# smart_bldc_commutator.net
KiCad netlist of a schematic drawn in EAGLE
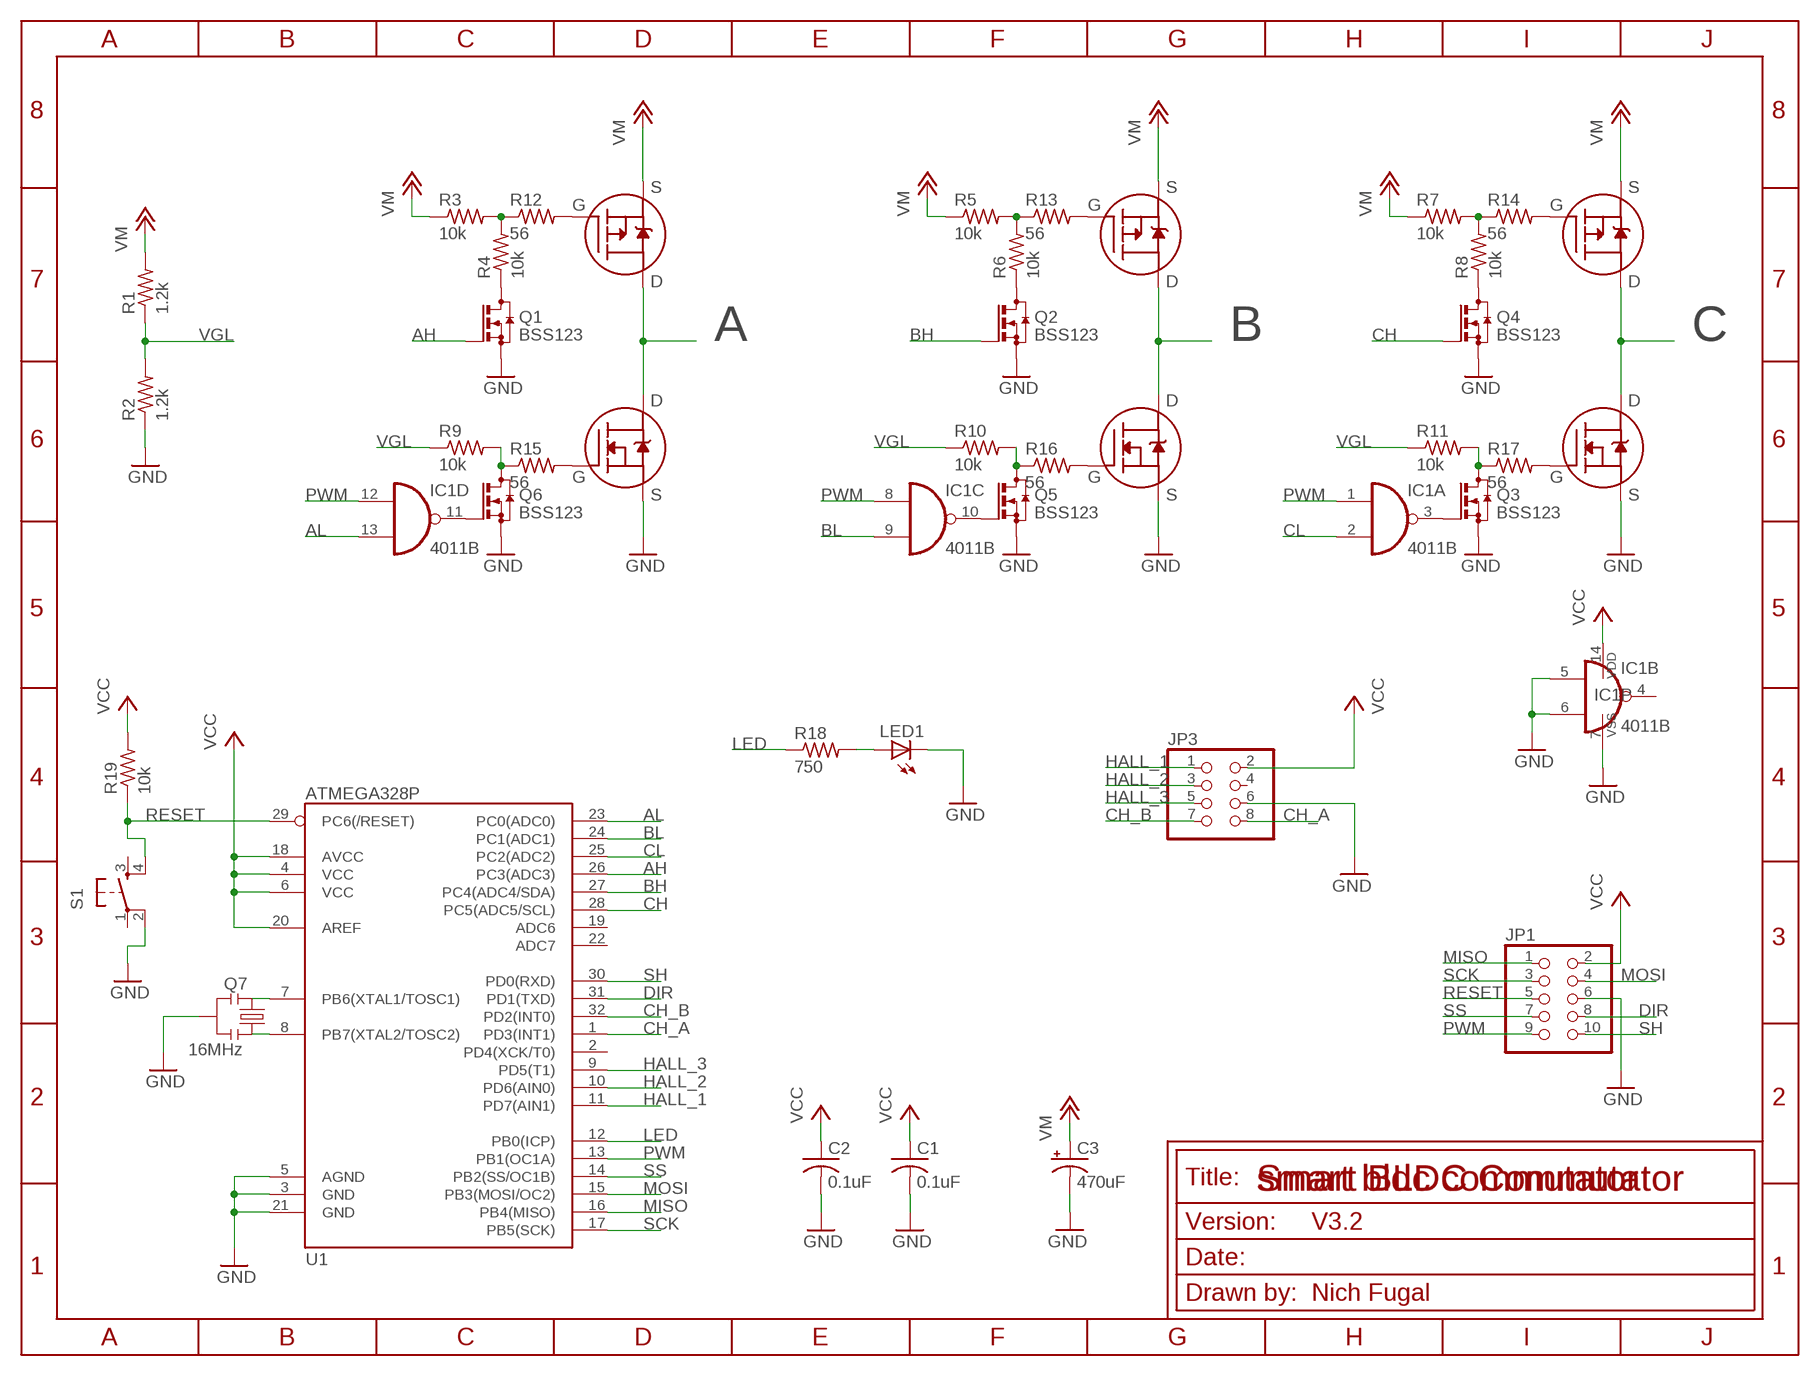
[diagram p0: schematic, sheet 1]

(export (version "E")
  (design (tool "Eeschema 10.0.6"))
  (components
    (comp (ref "C1")
      (value "0.1uF")
      (footprint "eagle-import:C0805")
      (libsource (lib "eagle-import") (part "C-USC0805"))
    )
    (comp (ref "C2")
      (value "0.1uF")
      (footprint "eagle-import:C0805")
      (libsource (lib "eagle-import") (part "C-USC0805"))
    )
    (comp (ref "C3")
      (value "470uF")
      (footprint "eagle-import:E5-10,5")
      (libsource (lib "eagle-import") (part "CPOL-USE5-10.5"))
    )
    (comp (ref "IC1")
      (value "4011B")
      (footprint "eagle-import:SO14")
      (libsource (lib "eagle-import") (part "4011D"))
    )
    (comp (ref "JP1")
      (value "PINHD-2X5")
      (footprint "eagle-import:2X05")
      (libsource (lib "eagle-import") (part "PINHD-2X5"))
    )
    (comp (ref "JP3")
      (value "PINHD-2X4")
      (footprint "eagle-import:2X04")
      (libsource (lib "eagle-import") (part "PINHD-2X4"))
    )
    (comp (ref "LED1")
      (value "LEDCHIP-LED0805")
      (footprint "eagle-import:CHIP-LED0805")
      (libsource (lib "eagle-import") (part "LEDCHIP-LED0805"))
    )
    (comp (ref "Q1")
      (value "BSS123")
      (footprint "eagle-import:SOT23")
      (libsource (lib "eagle-import") (part "BSS123"))
    )
    (comp (ref "Q2")
      (value "BSS123")
      (footprint "eagle-import:SOT23")
      (libsource (lib "eagle-import") (part "BSS123"))
    )
    (comp (ref "Q3")
      (value "BSS123")
      (footprint "eagle-import:SOT23")
      (libsource (lib "eagle-import") (part "BSS123"))
    )
    (comp (ref "Q4")
      (value "BSS123")
      (footprint "eagle-import:SOT23")
      (libsource (lib "eagle-import") (part "BSS123"))
    )
    (comp (ref "Q5")
      (value "BSS123")
      (footprint "eagle-import:SOT23")
      (libsource (lib "eagle-import") (part "BSS123"))
    )
    (comp (ref "Q6")
      (value "BSS123")
      (footprint "eagle-import:SOT23")
      (libsource (lib "eagle-import") (part "BSS123"))
    )
    (comp (ref "Q7")
      (value "16MHz")
      (footprint "eagle-import:RESONATOR-SMD")
      (libsource (lib "eagle-import") (part "RESONATORSMD"))
    )
    (comp (ref "R1")
      (value "1.2k")
      (footprint "eagle-import:R0805")
      (libsource (lib "eagle-import") (part "R-US_R0805"))
    )
    (comp (ref "R2")
      (value "1.2k")
      (footprint "eagle-import:R0805")
      (libsource (lib "eagle-import") (part "R-US_R0805"))
    )
    (comp (ref "R3")
      (value "10k")
      (footprint "eagle-import:R0805")
      (libsource (lib "eagle-import") (part "R-US_R0805"))
    )
    (comp (ref "R4")
      (value "10k")
      (footprint "eagle-import:R0805")
      (libsource (lib "eagle-import") (part "R-US_R0805"))
    )
    (comp (ref "R5")
      (value "10k")
      (footprint "eagle-import:R0805")
      (libsource (lib "eagle-import") (part "R-US_R0805"))
    )
    (comp (ref "R6")
      (value "10k")
      (footprint "eagle-import:R0805")
      (libsource (lib "eagle-import") (part "R-US_R0805"))
    )
    (comp (ref "R7")
      (value "10k")
      (footprint "eagle-import:R0805")
      (libsource (lib "eagle-import") (part "R-US_R0805"))
    )
    (comp (ref "R8")
      (value "10k")
      (footprint "eagle-import:R0805")
      (libsource (lib "eagle-import") (part "R-US_R0805"))
    )
    (comp (ref "R9")
      (value "10k")
      (footprint "eagle-import:R0805")
      (libsource (lib "eagle-import") (part "R-US_R0805"))
    )
    (comp (ref "R10")
      (value "10k")
      (footprint "eagle-import:R0805")
      (libsource (lib "eagle-import") (part "R-US_R0805"))
    )
    (comp (ref "R11")
      (value "10k")
      (footprint "eagle-import:R0805")
      (libsource (lib "eagle-import") (part "R-US_R0805"))
    )
    (comp (ref "R12")
      (value "56")
      (footprint "eagle-import:R0805")
      (libsource (lib "eagle-import") (part "R-US_R0805"))
    )
    (comp (ref "R13")
      (value "56")
      (footprint "eagle-import:R0805")
      (libsource (lib "eagle-import") (part "R-US_R0805"))
    )
    (comp (ref "R14")
      (value "56")
      (footprint "eagle-import:R0805")
      (libsource (lib "eagle-import") (part "R-US_R0805"))
    )
    (comp (ref "R15")
      (value "56")
      (footprint "eagle-import:R0805")
      (libsource (lib "eagle-import") (part "R-US_R0805"))
    )
    (comp (ref "R16")
      (value "56")
      (footprint "eagle-import:R0805")
      (libsource (lib "eagle-import") (part "R-US_R0805"))
    )
    (comp (ref "R17")
      (value "56")
      (footprint "eagle-import:R0805")
      (libsource (lib "eagle-import") (part "R-US_R0805"))
    )
    (comp (ref "R18")
      (value "750")
      (footprint "eagle-import:R0805")
      (libsource (lib "eagle-import") (part "R-US_R0805"))
    )
    (comp (ref "R19")
      (value "10k")
      (footprint "eagle-import:R0805")
      (libsource (lib "eagle-import") (part "R-US_R0805"))
    )
    (comp (ref "S1")
      (value "TAC_SWITCHSMD")
      (footprint "eagle-import:TACTILE_SWITCH_SMD")
      (libsource (lib "eagle-import") (part "TAC_SWITCHSMD"))
    )
    (comp (ref "U$1")
      (value "IRF4905")
      (footprint "eagle-import:D2PAK")
      (libsource (lib "eagle-import") (part "IRF4905"))
    )
    (comp (ref "U$2")
      (value "IRF1404S")
      (footprint "eagle-import:D2PAK")
      (libsource (lib "eagle-import") (part "IRF1404S"))
    )
    (comp (ref "U$3")
      (value "IRF4905")
      (footprint "eagle-import:D2PAK")
      (libsource (lib "eagle-import") (part "IRF4905"))
    )
    (comp (ref "U$4")
      (value "IRF1404S")
      (footprint "eagle-import:D2PAK")
      (libsource (lib "eagle-import") (part "IRF1404S"))
    )
    (comp (ref "U$5")
      (value "IRF4905")
      (footprint "eagle-import:D2PAK")
      (libsource (lib "eagle-import") (part "IRF4905"))
    )
    (comp (ref "U$6")
      (value "IRF1404S")
      (footprint "eagle-import:D2PAK")
      (libsource (lib "eagle-import") (part "IRF1404S"))
    )
    (comp (ref "U1")
      (value "ATMEGA328P")
      (footprint "eagle-import:TQFP32-08")
      (libsource (lib "eagle-import") (part "ATMEGA168"))
    )
  )
  (nets
    (net (code "1") (name "/AH") (class "Default")
      (node (ref "Q1") (pin "1") (pinfunction "G_1") (pintype "passive"))
      (node (ref "U1") (pin "26") (pinfunction "PC3(ADC3)_26") (pintype "bidirectional"))
    )
    (net (code "2") (name "/AL") (class "Default")
      (node (ref "IC1") (pin "13") (pinfunction "I1_13") (pintype "input"))
      (node (ref "U1") (pin "23") (pinfunction "PC0(ADC0)_23") (pintype "bidirectional"))
    )
    (net (code "3") (name "/BH") (class "Default")
      (node (ref "Q2") (pin "1") (pinfunction "G_1") (pintype "passive"))
      (node (ref "U1") (pin "27") (pinfunction "PC4(ADC4/SDA)_27") (pintype "bidirectional"))
    )
    (net (code "4") (name "/BL") (class "Default")
      (node (ref "IC1") (pin "9") (pinfunction "I1_9") (pintype "input"))
      (node (ref "U1") (pin "24") (pinfunction "PC1(ADC1)_24") (pintype "bidirectional"))
    )
    (net (code "5") (name "/CH") (class "Default")
      (node (ref "Q4") (pin "1") (pinfunction "G_1") (pintype "passive"))
      (node (ref "U1") (pin "28") (pinfunction "PC5(ADC5/SCL)_28") (pintype "bidirectional"))
    )
    (net (code "6") (name "/CH_A") (class "Default")
      (node (ref "JP3") (pin "8") (pinfunction "8_8") (pintype "passive"))
      (node (ref "U1") (pin "1") (pinfunction "PD3(INT1)_1") (pintype "bidirectional"))
    )
    (net (code "7") (name "/CH_B") (class "Default")
      (node (ref "JP3") (pin "7") (pinfunction "7_7") (pintype "passive"))
      (node (ref "U1") (pin "32") (pinfunction "PD2(INT0)_32") (pintype "bidirectional"))
    )
    (net (code "8") (name "/CL") (class "Default")
      (node (ref "IC1") (pin "2") (pinfunction "I1_2") (pintype "input"))
      (node (ref "U1") (pin "25") (pinfunction "PC2(ADC2)_25") (pintype "bidirectional"))
    )
    (net (code "9") (name "/DIR") (class "Default")
      (node (ref "JP1") (pin "8") (pinfunction "8_8") (pintype "passive"))
      (node (ref "U1") (pin "31") (pinfunction "PD1(TXD)_31") (pintype "bidirectional"))
    )
    (net (code "10") (name "/HALL_1") (class "Default")
      (node (ref "JP3") (pin "1") (pinfunction "1_1") (pintype "passive"))
      (node (ref "U1") (pin "11") (pinfunction "PD7(AIN1)_11") (pintype "bidirectional"))
    )
    (net (code "11") (name "/HALL_2") (class "Default")
      (node (ref "JP3") (pin "3") (pinfunction "3_3") (pintype "passive"))
      (node (ref "U1") (pin "10") (pinfunction "PD6(AIN0)_10") (pintype "bidirectional"))
    )
    (net (code "12") (name "/HALL_3") (class "Default")
      (node (ref "JP3") (pin "5") (pinfunction "5_5") (pintype "passive"))
      (node (ref "U1") (pin "9") (pinfunction "PD5(T1)_9") (pintype "bidirectional"))
    )
    (net (code "13") (name "/LED") (class "Default")
      (node (ref "R18") (pin "1") (pinfunction "1_1") (pintype "passive"))
      (node (ref "U1") (pin "12") (pinfunction "PB0(ICP)_12") (pintype "bidirectional"))
    )
    (net (code "14") (name "/MISO") (class "Default")
      (node (ref "JP1") (pin "1") (pinfunction "1_1") (pintype "passive"))
      (node (ref "U1") (pin "16") (pinfunction "PB4(MISO)_16") (pintype "bidirectional"))
    )
    (net (code "15") (name "/MOSI") (class "Default")
      (node (ref "JP1") (pin "4") (pinfunction "4_4") (pintype "passive"))
      (node (ref "U1") (pin "15") (pinfunction "PB3(MOSI/OC2)_15") (pintype "bidirectional"))
    )
    (net (code "16") (name "/PWM") (class "Default")
      (node (ref "IC1") (pin "1") (pinfunction "I0_1") (pintype "input"))
      (node (ref "IC1") (pin "12") (pinfunction "I0_12") (pintype "input"))
      (node (ref "IC1") (pin "8") (pinfunction "I0_8") (pintype "input"))
      (node (ref "JP1") (pin "9") (pinfunction "9_9") (pintype "passive"))
      (node (ref "U1") (pin "13") (pinfunction "PB1(OC1A)_13") (pintype "bidirectional"))
    )
    (net (code "17") (name "/RESET") (class "Default")
      (node (ref "JP1") (pin "5") (pinfunction "5_5") (pintype "passive"))
      (node (ref "R19") (pin "1") (pinfunction "1_1") (pintype "passive"))
      (node (ref "S1") (pin "4") (pinfunction "4_4") (pintype "passive"))
      (node (ref "U1") (pin "29") (pinfunction "PC6(/RESET)_29") (pintype "bidirectional"))
    )
    (net (code "18") (name "/SCK") (class "Default")
      (node (ref "JP1") (pin "3") (pinfunction "3_3") (pintype "passive"))
      (node (ref "U1") (pin "17") (pinfunction "PB5(SCK)_17") (pintype "bidirectional"))
    )
    (net (code "19") (name "/SH") (class "Default")
      (node (ref "JP1") (pin "10") (pinfunction "10_10") (pintype "passive"))
      (node (ref "U1") (pin "30") (pinfunction "PD0(RXD)_30") (pintype "bidirectional"))
    )
    (net (code "20") (name "/SS") (class "Default")
      (node (ref "JP1") (pin "7") (pinfunction "7_7") (pintype "passive"))
      (node (ref "U1") (pin "14") (pinfunction "PB2(SS/OC1B)_14") (pintype "bidirectional"))
    )
    (net (code "21") (name "/VGL") (class "Default")
      (node (ref "R1") (pin "1") (pinfunction "1_1") (pintype "passive"))
      (node (ref "R10") (pin "1") (pinfunction "1_1") (pintype "passive"))
      (node (ref "R11") (pin "1") (pinfunction "1_1") (pintype "passive"))
      (node (ref "R2") (pin "2") (pinfunction "2_2") (pintype "passive"))
      (node (ref "R9") (pin "1") (pinfunction "1_1") (pintype "passive"))
    )
    (net (code "22") (name "GND") (class "Default")
      (node (ref "C1") (pin "2") (pinfunction "2_2") (pintype "passive"))
      (node (ref "C2") (pin "2") (pinfunction "2_2") (pintype "passive"))
      (node (ref "C3") (pin "-") (pinfunction "-_-") (pintype "passive"))
      (node (ref "IC1") (pin "5") (pinfunction "I0_5") (pintype "input"))
      (node (ref "IC1") (pin "6") (pinfunction "I1_6") (pintype "input"))
      (node (ref "IC1") (pin "7") (pinfunction "VSS_7") (pintype "power_in"))
      (node (ref "JP1") (pin "6") (pinfunction "6_6") (pintype "passive"))
      (node (ref "JP3") (pin "6") (pinfunction "6_6") (pintype "passive"))
      (node (ref "LED1") (pin "C") (pinfunction "C_C") (pintype "passive"))
      (node (ref "Q1") (pin "2") (pinfunction "S_2") (pintype "passive"))
      (node (ref "Q2") (pin "2") (pinfunction "S_2") (pintype "passive"))
      (node (ref "Q3") (pin "2") (pinfunction "S_2") (pintype "passive"))
      (node (ref "Q4") (pin "2") (pinfunction "S_2") (pintype "passive"))
      (node (ref "Q5") (pin "2") (pinfunction "S_2") (pintype "passive"))
      (node (ref "Q6") (pin "2") (pinfunction "S_2") (pintype "passive"))
      (node (ref "Q7") (pin "2") (pinfunction "2_2") (pintype "passive"))
      (node (ref "R2") (pin "1") (pinfunction "1_1") (pintype "passive"))
      (node (ref "S1") (pin "2") (pinfunction "2_2") (pintype "passive"))
      (node (ref "U$2") (pin "3") (pinfunction "S_3") (pintype "bidirectional"))
      (node (ref "U$4") (pin "3") (pinfunction "S_3") (pintype "bidirectional"))
      (node (ref "U$6") (pin "3") (pinfunction "S_3") (pintype "bidirectional"))
      (node (ref "U1") (pin "21") (pinfunction "GND_21") (pintype "bidirectional"))
      (node (ref "U1") (pin "3") (pinfunction "GND_3") (pintype "bidirectional"))
      (node (ref "U1") (pin "5") (pinfunction "AGND_5") (pintype "bidirectional"))
    )
    (net (code "23") (name "Net-(IC1A-O)") (class "Default")
      (node (ref "IC1") (pin "3") (pinfunction "O_3") (pintype "output"))
      (node (ref "Q3") (pin "1") (pinfunction "G_1") (pintype "passive"))
    )
    (net (code "24") (name "Net-(IC1C-O)") (class "Default")
      (node (ref "IC1") (pin "10") (pinfunction "O_10") (pintype "output"))
      (node (ref "Q5") (pin "1") (pinfunction "G_1") (pintype "passive"))
    )
    (net (code "25") (name "Net-(IC1D-O)") (class "Default")
      (node (ref "IC1") (pin "11") (pinfunction "O_11") (pintype "output"))
      (node (ref "Q6") (pin "1") (pinfunction "G_1") (pintype "passive"))
    )
    (net (code "26") (name "Net-(LED1-PadA)") (class "Default")
      (node (ref "LED1") (pin "A") (pinfunction "A_A") (pintype "passive"))
      (node (ref "R18") (pin "2") (pinfunction "2_2") (pintype "passive"))
    )
    (net (code "27") (name "Net-(Q1-D)") (class "Default")
      (node (ref "Q1") (pin "3") (pinfunction "D_3") (pintype "passive"))
      (node (ref "R4") (pin "1") (pinfunction "1_1") (pintype "passive"))
    )
    (net (code "28") (name "Net-(Q2-D)") (class "Default")
      (node (ref "Q2") (pin "3") (pinfunction "D_3") (pintype "passive"))
      (node (ref "R6") (pin "1") (pinfunction "1_1") (pintype "passive"))
    )
    (net (code "29") (name "Net-(Q3-D)") (class "Default")
      (node (ref "Q3") (pin "3") (pinfunction "D_3") (pintype "passive"))
      (node (ref "R11") (pin "2") (pinfunction "2_2") (pintype "passive"))
      (node (ref "R17") (pin "1") (pinfunction "1_1") (pintype "passive"))
    )
    (net (code "30") (name "Net-(Q4-D)") (class "Default")
      (node (ref "Q4") (pin "3") (pinfunction "D_3") (pintype "passive"))
      (node (ref "R8") (pin "1") (pinfunction "1_1") (pintype "passive"))
    )
    (net (code "31") (name "Net-(Q5-D)") (class "Default")
      (node (ref "Q5") (pin "3") (pinfunction "D_3") (pintype "passive"))
      (node (ref "R10") (pin "2") (pinfunction "2_2") (pintype "passive"))
      (node (ref "R16") (pin "1") (pinfunction "1_1") (pintype "passive"))
    )
    (net (code "32") (name "Net-(Q6-D)") (class "Default")
      (node (ref "Q6") (pin "3") (pinfunction "D_3") (pintype "passive"))
      (node (ref "R15") (pin "1") (pinfunction "1_1") (pintype "passive"))
      (node (ref "R9") (pin "2") (pinfunction "2_2") (pintype "passive"))
    )
    (net (code "33") (name "Net-(R12-Pad1)") (class "Default")
      (node (ref "R12") (pin "1") (pinfunction "1_1") (pintype "passive"))
      (node (ref "R3") (pin "2") (pinfunction "2_2") (pintype "passive"))
      (node (ref "R4") (pin "2") (pinfunction "2_2") (pintype "passive"))
    )
    (net (code "34") (name "Net-(R13-Pad1)") (class "Default")
      (node (ref "R13") (pin "1") (pinfunction "1_1") (pintype "passive"))
      (node (ref "R5") (pin "2") (pinfunction "2_2") (pintype "passive"))
      (node (ref "R6") (pin "2") (pinfunction "2_2") (pintype "passive"))
    )
    (net (code "35") (name "Net-(R14-Pad1)") (class "Default")
      (node (ref "R14") (pin "1") (pinfunction "1_1") (pintype "passive"))
      (node (ref "R7") (pin "2") (pinfunction "2_2") (pintype "passive"))
      (node (ref "R8") (pin "2") (pinfunction "2_2") (pintype "passive"))
    )
    (net (code "36") (name "Net-(U$1-D)") (class "Default")
      (node (ref "U$1") (pin "2") (pinfunction "D_2") (pintype "bidirectional"))
      (node (ref "U$2") (pin "2") (pinfunction "D_2") (pintype "bidirectional"))
    )
    (net (code "37") (name "Net-(U$1-G)") (class "Default")
      (node (ref "R12") (pin "2") (pinfunction "2_2") (pintype "passive"))
      (node (ref "U$1") (pin "1") (pinfunction "G_1") (pintype "bidirectional"))
    )
    (net (code "38") (name "Net-(U$2-G)") (class "Default")
      (node (ref "R15") (pin "2") (pinfunction "2_2") (pintype "passive"))
      (node (ref "U$2") (pin "1") (pinfunction "G_1") (pintype "bidirectional"))
    )
    (net (code "39") (name "Net-(U$3-D)") (class "Default")
      (node (ref "U$3") (pin "2") (pinfunction "D_2") (pintype "bidirectional"))
      (node (ref "U$4") (pin "2") (pinfunction "D_2") (pintype "bidirectional"))
    )
    (net (code "40") (name "Net-(U$3-G)") (class "Default")
      (node (ref "R13") (pin "2") (pinfunction "2_2") (pintype "passive"))
      (node (ref "U$3") (pin "1") (pinfunction "G_1") (pintype "bidirectional"))
    )
    (net (code "41") (name "Net-(U$4-G)") (class "Default")
      (node (ref "R16") (pin "2") (pinfunction "2_2") (pintype "passive"))
      (node (ref "U$4") (pin "1") (pinfunction "G_1") (pintype "bidirectional"))
    )
    (net (code "42") (name "Net-(U$5-D)") (class "Default")
      (node (ref "U$5") (pin "2") (pinfunction "D_2") (pintype "bidirectional"))
      (node (ref "U$6") (pin "2") (pinfunction "D_2") (pintype "bidirectional"))
    )
    (net (code "43") (name "Net-(U$5-G)") (class "Default")
      (node (ref "R14") (pin "2") (pinfunction "2_2") (pintype "passive"))
      (node (ref "U$5") (pin "1") (pinfunction "G_1") (pintype "bidirectional"))
    )
    (net (code "44") (name "Net-(U$6-G)") (class "Default")
      (node (ref "R17") (pin "2") (pinfunction "2_2") (pintype "passive"))
      (node (ref "U$6") (pin "1") (pinfunction "G_1") (pintype "bidirectional"))
    )
    (net (code "45") (name "Net-(U1-PB6(XTAL1{slash}TOSC1))") (class "Default")
      (node (ref "Q7") (pin "3") (pinfunction "3_3") (pintype "passive"))
      (node (ref "U1") (pin "7") (pinfunction "PB6(XTAL1/TOSC1)_7") (pintype "bidirectional"))
    )
    (net (code "46") (name "Net-(U1-PB7(XTAL2{slash}TOSC2))") (class "Default")
      (node (ref "Q7") (pin "1") (pinfunction "1_1") (pintype "passive"))
      (node (ref "U1") (pin "8") (pinfunction "PB7(XTAL2/TOSC2)_8") (pintype "bidirectional"))
    )
    (net (code "47") (name "VCC") (class "Default")
      (node (ref "C1") (pin "1") (pinfunction "1_1") (pintype "passive"))
      (node (ref "C2") (pin "1") (pinfunction "1_1") (pintype "passive"))
      (node (ref "IC1") (pin "14") (pinfunction "VDD_14") (pintype "power_in"))
      (node (ref "JP1") (pin "2") (pinfunction "2_2") (pintype "passive"))
      (node (ref "JP3") (pin "2") (pinfunction "2_2") (pintype "passive"))
      (node (ref "R19") (pin "2") (pinfunction "2_2") (pintype "passive"))
      (node (ref "U1") (pin "18") (pinfunction "AVCC_18") (pintype "bidirectional"))
      (node (ref "U1") (pin "20") (pinfunction "AREF_20") (pintype "bidirectional"))
      (node (ref "U1") (pin "4") (pinfunction "VCC_4") (pintype "bidirectional"))
      (node (ref "U1") (pin "6") (pinfunction "VCC_6") (pintype "bidirectional"))
    )
    (net (code "48") (name "VM") (class "Default")
      (node (ref "C3") (pin "+") (pinfunction "+_+") (pintype "passive"))
      (node (ref "R1") (pin "2") (pinfunction "2_2") (pintype "passive"))
      (node (ref "R3") (pin "1") (pinfunction "1_1") (pintype "passive"))
      (node (ref "R5") (pin "1") (pinfunction "1_1") (pintype "passive"))
      (node (ref "R7") (pin "1") (pinfunction "1_1") (pintype "passive"))
      (node (ref "U$1") (pin "3") (pinfunction "S_3") (pintype "bidirectional"))
      (node (ref "U$3") (pin "3") (pinfunction "S_3") (pintype "bidirectional"))
      (node (ref "U$5") (pin "3") (pinfunction "S_3") (pintype "bidirectional"))
    )
    (net (code "49") (name "unconnected-(IC1B-O-Pad4)") (class "Default")
      (node (ref "IC1") (pin "4") (pinfunction "O_4") (pintype "output"))
    )
    (net (code "50") (name "unconnected-(JP3-Pad4)") (class "Default")
      (node (ref "JP3") (pin "4") (pinfunction "4_4") (pintype "passive"))
    )
    (net (code "51") (name "unconnected-(S1-Pad1)") (class "Default")
      (node (ref "S1") (pin "1") (pinfunction "1_1") (pintype "passive"))
    )
    (net (code "52") (name "unconnected-(S1-Pad3)") (class "Default")
      (node (ref "S1") (pin "3") (pinfunction "3_3") (pintype "passive"))
    )
    (net (code "53") (name "unconnected-(U1-ADC6-Pad19)") (class "Default")
      (node (ref "U1") (pin "19") (pinfunction "ADC6_19") (pintype "bidirectional"))
    )
    (net (code "54") (name "unconnected-(U1-ADC7-Pad22)") (class "Default")
      (node (ref "U1") (pin "22") (pinfunction "ADC7_22") (pintype "bidirectional"))
    )
    (net (code "55") (name "unconnected-(U1-PD4(XCK{slash}T0)-Pad2)") (class "Default")
      (node (ref "U1") (pin "2") (pinfunction "PD4(XCK/T0)_2") (pintype "bidirectional"))
    )
  )
)
